# Top.net
KiCad netlist of a schematic drawn in Altium Designer
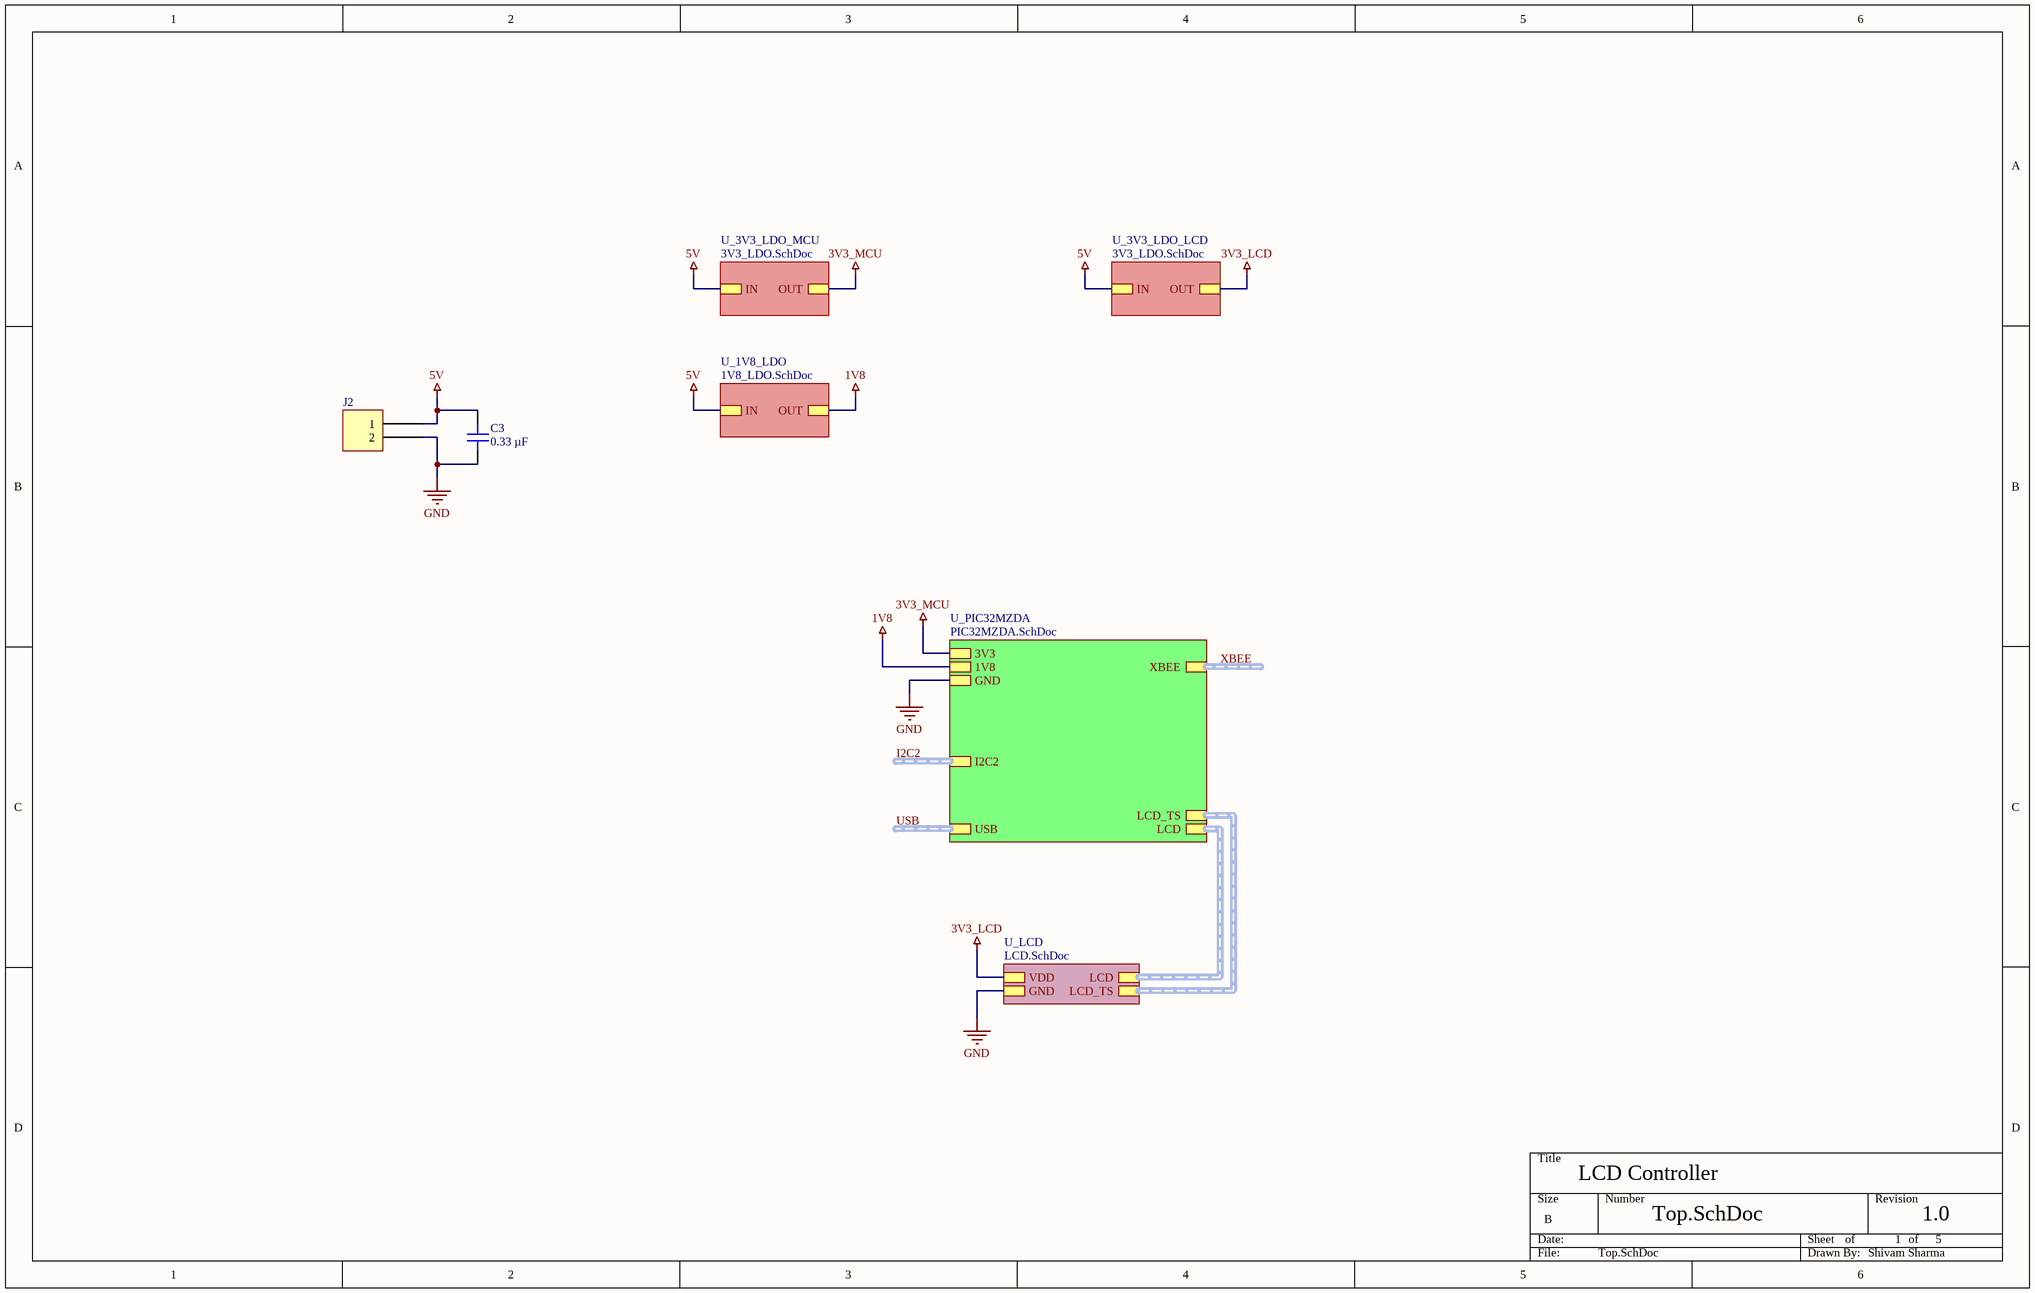
[diagram p0: Top.SchDoc]

(export (version "E")
  (design (tool "Eeschema 10.0.6"))
  (components
    (comp (ref "C3")
      (value "0.33 µF")
      (footprint "CAP 0603_1608")
      (description "CAP CER 0.33UF 10V X7R 0603")
      (fields
        (field (name "PART NUMBER") "CL10B334KP8NNNC")
        (field (name "MANUFACTURER") "Samsung Electro-Mechanics")
      )
      (libsource (lib "Celestial Altium Library - altium_library") (part "Capacitor"))
    )
    (comp (ref "J2")
      (value "S2B-PH-SM4-TB(LF)(SN)")
      (footprint "JST S2B-PH-SM4-TB")
      (description "CONN HEADER SMD R/A 2POS 2MM")
      (fields (field (name "MANUFACTURER") "JST Sales America Inc."))
      (libsource (lib "Celestial Altium Library - altium_library") (part "2 Pin"))
    )
  )
  (nets
    (net (code "12") (name "5V") (class "Default")
      (node (ref "C3") (pin "2") (pinfunction "2_2") (pintype "passive"))
      (node (ref "J2") (pin "1") (pinfunction "1_1") (pintype "passive"))
    )
    (net (code "13") (name "GND") (class "Default")
      (node (ref "C3") (pin "1") (pinfunction "1_1") (pintype "passive"))
      (node (ref "J2") (pin "2") (pinfunction "2_2") (pintype "passive"))
    )
  )
)
